# fantimer.net
KiCad netlist of a schematic drawn in EAGLE
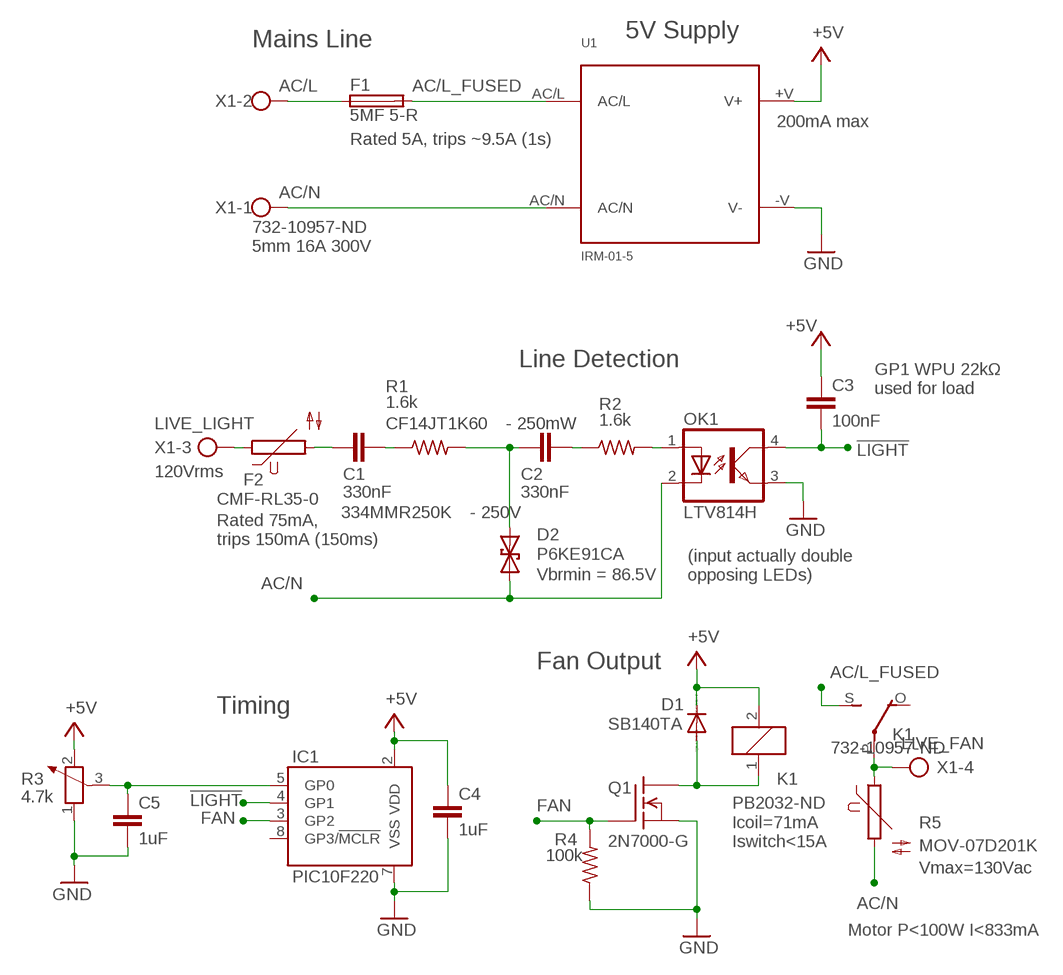
[diagram p0: schematic, sheet 1]

(export (version "E")
  (design (tool "Eeschema 10.0.6"))
  (components
    (comp (ref "C1")
      (value "330nF")
      (footprint "eagle-import:C102-064X133")
      (libsource (lib "eagle-import") (part "C-EU102-064X133"))
    )
    (comp (ref "C2")
      (value "330nF")
      (footprint "eagle-import:C102-064X133")
      (libsource (lib "eagle-import") (part "C-EU102-064X133"))
    )
    (comp (ref "C3")
      (value "100nF")
      (footprint "eagle-import:C025-025X050")
      (libsource (lib "eagle-import") (part "C-EU025-025X050"))
    )
    (comp (ref "C4")
      (value "1uF")
      (footprint "eagle-import:C025-025X050")
      (libsource (lib "eagle-import") (part "C-EU025-025X050"))
    )
    (comp (ref "C5")
      (value "1uF")
      (footprint "eagle-import:C025-025X050")
      (libsource (lib "eagle-import") (part "C-EU025-025X050"))
    )
    (comp (ref "D1")
      (value "SB140TA")
      (footprint "eagle-import:DO41-7.6")
      (libsource (lib "eagle-import") (part "DIODE-DO41-7.6"))
    )
    (comp (ref "D2")
      (value "P6KE91CA")
      (footprint "eagle-import:CB417-15")
      (libsource (lib "eagle-import") (part "P6KEXXC"))
    )
    (comp (ref "F1")
      (value "5MF 5-R")
      (footprint "eagle-import:SHK20Q")
      (libsource (lib "eagle-import") (part "FUSESHK20Q"))
    )
    (comp (ref "F2")
      (value "CMF-RL35-0")
      (footprint "eagle-import:S05K11")
      (libsource (lib "eagle-import") (part "S05K11"))
    )
    (comp (ref "IC1")
      (value "PIC10F220")
      (footprint "eagle-import:DIL08")
      (libsource (lib "eagle-import") (part "PIC10F220-I/P"))
    )
    (comp (ref "K1")
      (value "PB2032-ND")
      (footprint "eagle-import:G5LE")
      (libsource (lib "eagle-import") (part "G5LE"))
    )
    (comp (ref "OK1")
      (value "LTV814H")
      (footprint "eagle-import:DIL04")
      (libsource (lib "eagle-import") (part "LTV816"))
    )
    (comp (ref "Q1")
      (value "2N7000-G")
      (footprint "eagle-import:TO237")
      (libsource (lib "eagle-import") (part "VN2222KM"))
    )
    (comp (ref "R1")
      (value "1.6k")
      (footprint "eagle-import:0207_7")
      (libsource (lib "eagle-import") (part "R-US_0207/7"))
    )
    (comp (ref "R2")
      (value "1.6k")
      (footprint "eagle-import:0207_7")
      (libsource (lib "eagle-import") (part "R-US_0207/7"))
    )
    (comp (ref "R3")
      (value "4.7k")
      (footprint "eagle-import:PT-10")
      (libsource (lib "eagle-import") (part "POTENTIOMETER_PT-10"))
    )
    (comp (ref "R4")
      (value "100k")
      (footprint "eagle-import:0207_7")
      (libsource (lib "eagle-import") (part "R-US_0207/7"))
    )
    (comp (ref "R5")
      (value "MOV-07D201K")
      (footprint "eagle-import:S05K11")
      (libsource (lib "eagle-import") (part "S05K11"))
    )
    (comp (ref "U1")
      (value "IRM-01-5")
      (footprint "eagle-import:IRM-01-X")
      (libsource (lib "eagle-import") (part "IRM-01-5"))
    )
    (comp (ref "X1")
      (value "732-10957-ND")
      (footprint "eagle-import:W237-4")
      (libsource (lib "eagle-import") (part "W237-4"))
    )
  )
  (nets
    (net (code "1") (name "+5V") (class "Default")
      (node (ref "C3") (pin "1") (pinfunction "1_1") (pintype "passive"))
      (node (ref "C4") (pin "1") (pinfunction "1_1") (pintype "passive"))
      (node (ref "D1") (pin "C") (pinfunction "C_C") (pintype "passive"))
      (node (ref "IC1") (pin "2") (pinfunction "VDD_2") (pintype "power_in"))
      (node (ref "K1") (pin "2") (pinfunction "2_2") (pintype "passive"))
      (node (ref "R3") (pin "2") (pinfunction "2_2") (pintype "passive"))
      (node (ref "U1") (pin "+V") (pinfunction "V+_+V") (pintype "power_in"))
    )
    (net (code "2") (name "/AC{slash}L") (class "Default")
      (node (ref "F1") (pin "1A") (pinfunction "1_1A") (pintype "passive"))
      (node (ref "X1") (pin "2") (pinfunction "KL_2") (pintype "passive"))
    )
    (net (code "3") (name "/AC{slash}L_FUSED") (class "Default")
      (node (ref "F1") (pin "2A") (pinfunction "2_2A") (pintype "passive"))
      (node (ref "K1") (pin "S") (pinfunction "S_S") (pintype "passive"))
      (node (ref "U1") (pin "AC/L") (pinfunction "AC/L_AC/L") (pintype "power_in"))
    )
    (net (code "4") (name "/AC{slash}N") (class "Default")
      (node (ref "D2") (pin "A") (pinfunction "1_A") (pintype "passive"))
      (node (ref "OK1") (pin "2") (pinfunction "C_2") (pintype "passive"))
      (node (ref "R5") (pin "2") (pinfunction "2_2") (pintype "passive"))
      (node (ref "U1") (pin "AC/N") (pinfunction "AC/N_AC/N") (pintype "power_in"))
      (node (ref "X1") (pin "1") (pinfunction "KL_1") (pintype "passive"))
    )
    (net (code "5") (name "/FAN") (class "Default")
      (node (ref "IC1") (pin "3") (pinfunction "GP2_3") (pintype "bidirectional"))
      (node (ref "Q1") (pin "2") (pinfunction "G_2") (pintype "passive"))
      (node (ref "R4") (pin "2") (pinfunction "2_2") (pintype "passive"))
    )
    (net (code "6") (name "/LIVE_FAN") (class "Default")
      (node (ref "K1") (pin "P") (pinfunction "P_P") (pintype "passive"))
      (node (ref "R5") (pin "1") (pinfunction "1_1") (pintype "passive"))
      (node (ref "X1") (pin "4") (pinfunction "KL_4") (pintype "passive"))
    )
    (net (code "7") (name "/LIVE_LIGHT") (class "Default")
      (node (ref "F2") (pin "1") (pinfunction "1_1") (pintype "passive"))
      (node (ref "X1") (pin "3") (pinfunction "KL_3") (pintype "passive"))
    )
    (net (code "8") (name "/~{LIGHT}") (class "Default")
      (node (ref "C3") (pin "2") (pinfunction "2_2") (pintype "passive"))
      (node (ref "IC1") (pin "4") (pinfunction "GP1_4") (pintype "bidirectional"))
      (node (ref "OK1") (pin "4") (pinfunction "COL_4") (pintype "passive"))
    )
    (net (code "9") (name "GND") (class "Default")
      (node (ref "C4") (pin "2") (pinfunction "2_2") (pintype "passive"))
      (node (ref "C5") (pin "2") (pinfunction "2_2") (pintype "passive"))
      (node (ref "IC1") (pin "7") (pinfunction "VSS_7") (pintype "power_in"))
      (node (ref "OK1") (pin "3") (pinfunction "EMIT_3") (pintype "passive"))
      (node (ref "Q1") (pin "3") (pinfunction "S_3") (pintype "passive"))
      (node (ref "R3") (pin "1") (pinfunction "1_1") (pintype "passive"))
      (node (ref "R4") (pin "1") (pinfunction "1_1") (pintype "passive"))
      (node (ref "U1") (pin "-V") (pinfunction "V-_-V") (pintype "power_in"))
    )
    (net (code "10") (name "Net-(C1-Pad1)") (class "Default")
      (node (ref "C1") (pin "1") (pinfunction "1_1") (pintype "passive"))
      (node (ref "F2") (pin "2") (pinfunction "2_2") (pintype "passive"))
    )
    (net (code "11") (name "Net-(C1-Pad2)") (class "Default")
      (node (ref "C1") (pin "2") (pinfunction "2_2") (pintype "passive"))
      (node (ref "R1") (pin "1") (pinfunction "1_1") (pintype "passive"))
    )
    (net (code "12") (name "Net-(C2-Pad2)") (class "Default")
      (node (ref "C2") (pin "2") (pinfunction "2_2") (pintype "passive"))
      (node (ref "R2") (pin "1") (pinfunction "1_1") (pintype "passive"))
    )
    (net (code "13") (name "Net-(D2-2)") (class "Default")
      (node (ref "C2") (pin "1") (pinfunction "1_1") (pintype "passive"))
      (node (ref "D2") (pin "C") (pinfunction "2_C") (pintype "passive"))
      (node (ref "R1") (pin "2") (pinfunction "2_2") (pintype "passive"))
    )
    (net (code "14") (name "Net-(IC1-GP0)") (class "Default")
      (node (ref "C5") (pin "1") (pinfunction "1_1") (pintype "passive"))
      (node (ref "IC1") (pin "5") (pinfunction "GP0_5") (pintype "bidirectional"))
      (node (ref "R3") (pin "3") (pinfunction "3_3") (pintype "passive"))
    )
    (net (code "15") (name "Net-(OK1-A)") (class "Default")
      (node (ref "OK1") (pin "1") (pinfunction "A_1") (pintype "passive"))
      (node (ref "R2") (pin "2") (pinfunction "2_2") (pintype "passive"))
    )
    (net (code "16") (name "Net-(Q1-D)") (class "Default")
      (node (ref "D1") (pin "A") (pinfunction "A_A") (pintype "passive"))
      (node (ref "K1") (pin "1") (pinfunction "1_1") (pintype "passive"))
      (node (ref "Q1") (pin "1") (pinfunction "D_1") (pintype "passive"))
    )
    (net (code "17") (name "unconnected-(IC1-GP3{slash}~{MCLR}-Pad8)") (class "Default")
      (node (ref "IC1") (pin "8") (pinfunction "GP3/~{MCLR}_8") (pintype "input"))
    )
    (net (code "18") (name "unconnected-(K1-PadO)") (class "Default")
      (node (ref "K1") (pin "O") (pinfunction "O_O") (pintype "passive"))
    )
  )
)
